# breakout_v0_3.net
KiCad netlist of a schematic drawn in EAGLE
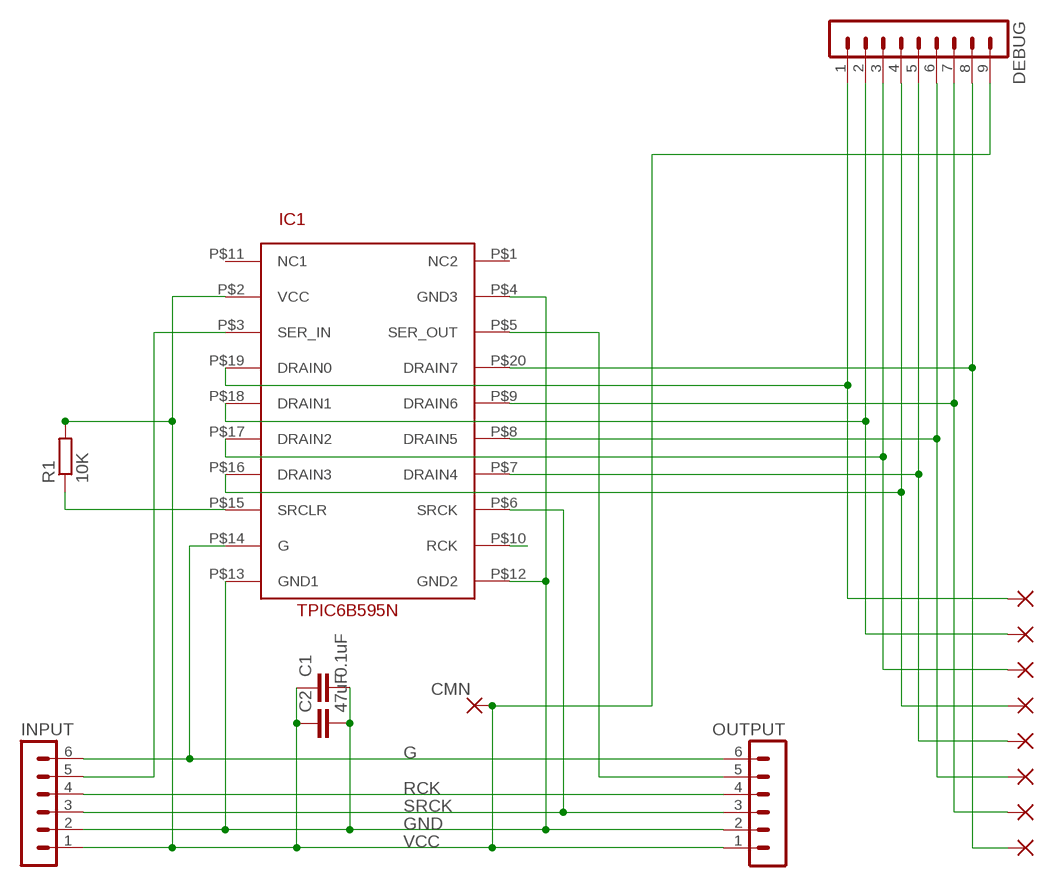
[diagram p0: schematic, sheet 1]

(export (version "E")
  (design (tool "Eeschema 10.0.6"))
  (components
    (comp (ref "C1")
      (value "0.1uF")
      (footprint "eagle-import:C025-025X050")
      (libsource (lib "eagle-import") (part "C-EU025-025X050"))
    )
    (comp (ref "C2")
      (value "47uF")
      (footprint "eagle-import:C025-025X050")
      (libsource (lib "eagle-import") (part "C-EU025-025X050"))
    )
    (comp (ref "CMN")
      (value "1,6/0,8")
      (footprint "eagle-import:1,6_0,8")
      (libsource (lib "eagle-import") (part "1,6/0,8"))
    )
    (comp (ref "DEBUG")
      (value "MA09-1")
      (footprint "eagle-import:MA09-1")
      (libsource (lib "eagle-import") (part "MA09-1"))
    )
    (comp (ref "DEC")
      (value "1,6/0,8")
      (footprint "eagle-import:1,6_0,8")
      (libsource (lib "eagle-import") (part "1,6/0,8"))
    )
    (comp (ref "INPUT")
      (value "MA06-1")
      (footprint "eagle-import:MA06-1")
      (libsource (lib "eagle-import") (part "MA06-1"))
    )
    (comp (ref "OUTPUT")
      (value "MA06-1")
      (footprint "eagle-import:MA06-1")
      (libsource (lib "eagle-import") (part "MA06-1"))
    )
    (comp (ref "R1")
      (value "10K")
      (footprint "eagle-import:0207_7")
      (libsource (lib "eagle-import") (part "R-EU_0207/7"))
    )
    (comp (ref "SEGA")
      (value "1,6/0,8")
      (footprint "eagle-import:1,6_0,8")
      (libsource (lib "eagle-import") (part "1,6/0,8"))
    )
    (comp (ref "SEGB")
      (value "1,6/0,8")
      (footprint "eagle-import:1,6_0,8")
      (libsource (lib "eagle-import") (part "1,6/0,8"))
    )
    (comp (ref "SEGC")
      (value "1,6/0,8")
      (footprint "eagle-import:1,6_0,8")
      (libsource (lib "eagle-import") (part "1,6/0,8"))
    )
    (comp (ref "SEGD")
      (value "1,6/0,8")
      (footprint "eagle-import:1,6_0,8")
      (libsource (lib "eagle-import") (part "1,6/0,8"))
    )
    (comp (ref "SEGE")
      (value "1,6/0,8")
      (footprint "eagle-import:1,6_0,8")
      (libsource (lib "eagle-import") (part "1,6/0,8"))
    )
    (comp (ref "SEGF")
      (value "1,6/0,8")
      (footprint "eagle-import:1,6_0,8")
      (libsource (lib "eagle-import") (part "1,6/0,8"))
    )
    (comp (ref "SEGG")
      (value "1,6/0,8")
      (footprint "eagle-import:1,6_0,8")
      (libsource (lib "eagle-import") (part "1,6/0,8"))
    )
    (comp (ref "U$1")
      (value "TPIC6B595NPDIP-20")
      (footprint "eagle-import:PDIP-20")
      (libsource (lib "eagle-import") (part "TPIC6B595NPDIP-20"))
    )
  )
  (nets
    (net (code "1") (name "/G") (class "Default")
      (node (ref "INPUT") (pin "6") (pinfunction "6_6") (pintype "passive"))
      (node (ref "OUTPUT") (pin "6") (pinfunction "6_6") (pintype "passive"))
      (node (ref "U$1") (pin "P$14") (pinfunction "G_P$14") (pintype "bidirectional"))
    )
    (net (code "2") (name "/GND") (class "Default")
      (node (ref "C1") (pin "2") (pinfunction "2_2") (pintype "passive"))
      (node (ref "C2") (pin "2") (pinfunction "2_2") (pintype "passive"))
      (node (ref "INPUT") (pin "2") (pinfunction "2_2") (pintype "passive"))
      (node (ref "OUTPUT") (pin "2") (pinfunction "2_2") (pintype "passive"))
      (node (ref "U$1") (pin "P$12") (pinfunction "GND2_P$12") (pintype "bidirectional"))
      (node (ref "U$1") (pin "P$13") (pinfunction "GND1_P$13") (pintype "bidirectional"))
      (node (ref "U$1") (pin "P$4") (pinfunction "GND3_P$4") (pintype "bidirectional"))
    )
    (net (code "3") (name "/RCK") (class "Default")
      (node (ref "INPUT") (pin "4") (pinfunction "4_4") (pintype "passive"))
      (node (ref "OUTPUT") (pin "4") (pinfunction "4_4") (pintype "passive"))
    )
    (net (code "4") (name "/SRCK") (class "Default")
      (node (ref "INPUT") (pin "3") (pinfunction "3_3") (pintype "passive"))
      (node (ref "OUTPUT") (pin "3") (pinfunction "3_3") (pintype "passive"))
      (node (ref "U$1") (pin "P$6") (pinfunction "SRCK_P$6") (pintype "bidirectional"))
    )
    (net (code "5") (name "/VCC") (class "Default")
      (node (ref "C1") (pin "1") (pinfunction "1_1") (pintype "passive"))
      (node (ref "C2") (pin "1") (pinfunction "1_1") (pintype "passive"))
      (node (ref "CMN") (pin "1") (pinfunction "P_1") (pintype "passive"))
      (node (ref "DEBUG") (pin "9") (pinfunction "9_9") (pintype "passive"))
      (node (ref "INPUT") (pin "1") (pinfunction "1_1") (pintype "passive"))
      (node (ref "OUTPUT") (pin "1") (pinfunction "1_1") (pintype "passive"))
      (node (ref "R1") (pin "2") (pinfunction "2_2") (pintype "passive"))
      (node (ref "U$1") (pin "P$2") (pinfunction "VCC_P$2") (pintype "bidirectional"))
    )
    (net (code "6") (name "Net-(DEC-P)") (class "Default")
      (node (ref "DEBUG") (pin "8") (pinfunction "8_8") (pintype "passive"))
      (node (ref "DEC") (pin "1") (pinfunction "P_1") (pintype "passive"))
      (node (ref "U$1") (pin "P$20") (pinfunction "DRAIN7_P$20") (pintype "bidirectional"))
    )
    (net (code "7") (name "Net-(SEGA-P)") (class "Default")
      (node (ref "DEBUG") (pin "1") (pinfunction "1_1") (pintype "passive"))
      (node (ref "SEGA") (pin "1") (pinfunction "P_1") (pintype "passive"))
      (node (ref "U$1") (pin "P$19") (pinfunction "DRAIN0_P$19") (pintype "bidirectional"))
    )
    (net (code "8") (name "Net-(SEGB-P)") (class "Default")
      (node (ref "DEBUG") (pin "2") (pinfunction "2_2") (pintype "passive"))
      (node (ref "SEGB") (pin "1") (pinfunction "P_1") (pintype "passive"))
      (node (ref "U$1") (pin "P$18") (pinfunction "DRAIN1_P$18") (pintype "bidirectional"))
    )
    (net (code "9") (name "Net-(SEGC-P)") (class "Default")
      (node (ref "DEBUG") (pin "3") (pinfunction "3_3") (pintype "passive"))
      (node (ref "SEGC") (pin "1") (pinfunction "P_1") (pintype "passive"))
      (node (ref "U$1") (pin "P$17") (pinfunction "DRAIN2_P$17") (pintype "bidirectional"))
    )
    (net (code "10") (name "Net-(SEGD-P)") (class "Default")
      (node (ref "DEBUG") (pin "4") (pinfunction "4_4") (pintype "passive"))
      (node (ref "SEGD") (pin "1") (pinfunction "P_1") (pintype "passive"))
      (node (ref "U$1") (pin "P$16") (pinfunction "DRAIN3_P$16") (pintype "bidirectional"))
    )
    (net (code "11") (name "Net-(SEGE-P)") (class "Default")
      (node (ref "DEBUG") (pin "5") (pinfunction "5_5") (pintype "passive"))
      (node (ref "SEGE") (pin "1") (pinfunction "P_1") (pintype "passive"))
      (node (ref "U$1") (pin "P$7") (pinfunction "DRAIN4_P$7") (pintype "bidirectional"))
    )
    (net (code "12") (name "Net-(SEGF-P)") (class "Default")
      (node (ref "DEBUG") (pin "6") (pinfunction "6_6") (pintype "passive"))
      (node (ref "SEGF") (pin "1") (pinfunction "P_1") (pintype "passive"))
      (node (ref "U$1") (pin "P$8") (pinfunction "DRAIN5_P$8") (pintype "bidirectional"))
    )
    (net (code "13") (name "Net-(SEGG-P)") (class "Default")
      (node (ref "DEBUG") (pin "7") (pinfunction "7_7") (pintype "passive"))
      (node (ref "SEGG") (pin "1") (pinfunction "P_1") (pintype "passive"))
      (node (ref "U$1") (pin "P$9") (pinfunction "DRAIN6_P$9") (pintype "bidirectional"))
    )
    (net (code "14") (name "Net-(U$1-SER_IN)") (class "Default")
      (node (ref "INPUT") (pin "5") (pinfunction "5_5") (pintype "passive"))
      (node (ref "U$1") (pin "P$3") (pinfunction "SER_IN_P$3") (pintype "bidirectional"))
    )
    (net (code "15") (name "Net-(U$1-SER_OUT)") (class "Default")
      (node (ref "OUTPUT") (pin "5") (pinfunction "5_5") (pintype "passive"))
      (node (ref "U$1") (pin "P$5") (pinfunction "SER_OUT_P$5") (pintype "bidirectional"))
    )
    (net (code "16") (name "Net-(U$1-SRCLR)") (class "Default")
      (node (ref "R1") (pin "1") (pinfunction "1_1") (pintype "passive"))
      (node (ref "U$1") (pin "P$15") (pinfunction "SRCLR_P$15") (pintype "bidirectional"))
    )
    (net (code "17") (name "unconnected-(U$1-NC1-PadP$11)") (class "Default")
      (node (ref "U$1") (pin "P$11") (pinfunction "NC1_P$11") (pintype "bidirectional"))
    )
    (net (code "18") (name "unconnected-(U$1-NC2-PadP$1)") (class "Default")
      (node (ref "U$1") (pin "P$1") (pinfunction "NC2_P$1") (pintype "bidirectional"))
    )
    (net (code "19") (name "unconnected-(U$1-RCK-PadP$10)") (class "Default")
      (node (ref "U$1") (pin "P$10") (pinfunction "RCK_P$10") (pintype "bidirectional"))
    )
  )
)
